# Lora_Artemis_schematic.net
KiCad netlist of a schematic drawn in EAGLE
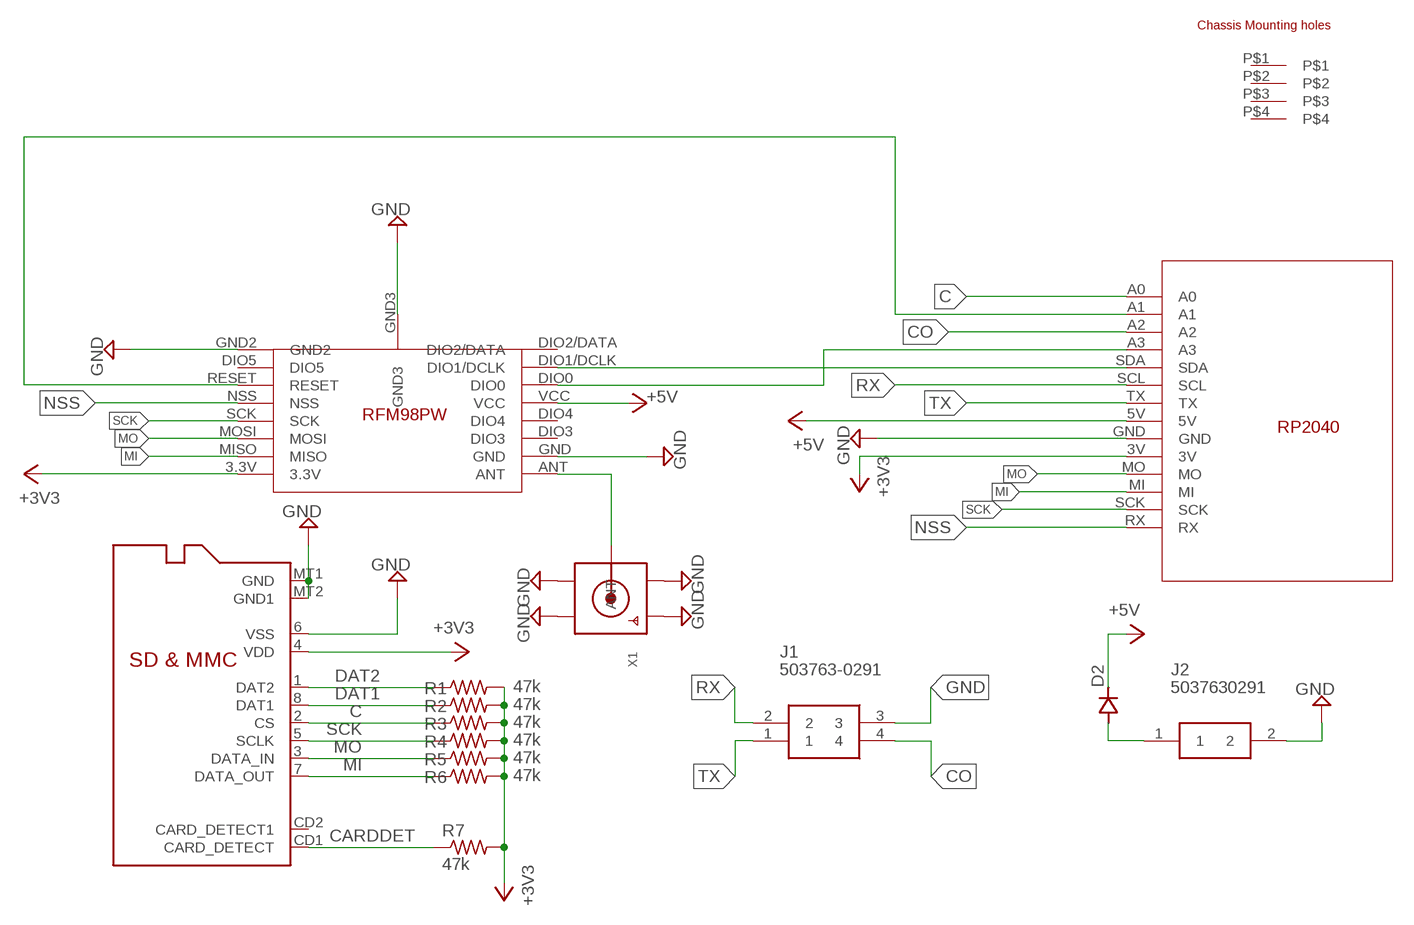
[diagram p0: schematic, sheet 1]

(export (version "E")
  (design (tool "Eeschema 10.0.6"))
  (components
    (comp (ref "D2")
      (value "DSOD323")
      (footprint "eagle-import:SOD323")
      (fields (field (name "MPN") "CDSOD323-T05C"))
      (libsource (lib "eagle-import") (part "DSOD323"))
    )
    (comp (ref "H1")
      (value "PC104_WCONN_2\"")
      (footprint "eagle-import:PC104_WCONN_2")
      (libsource (lib "eagle-import") (part "PC104_WCONN_2{dblquote}"))
    )
    (comp (ref "J1")
      (value "503763-0291")
      (footprint "eagle-import:5037630291")
      (fields (field (name "MOUSER_PART_NUMBER") "538-503763-0291"))
      (libsource (lib "eagle-import") (part "503763-0291"))
    )
    (comp (ref "J2")
      (value "5037630291")
      (footprint "eagle-import:5037630291")
      (libsource (lib "eagle-import") (part "5037630291"))
    )
    (comp (ref "R1")
      (value "47k")
      (footprint "eagle-import:M0805")
      (libsource (lib "eagle-import") (part "R-US_M0805"))
    )
    (comp (ref "R2")
      (value "47k")
      (footprint "eagle-import:M0805")
      (libsource (lib "eagle-import") (part "R-US_M0805"))
    )
    (comp (ref "R3")
      (value "47k")
      (footprint "eagle-import:M0805")
      (libsource (lib "eagle-import") (part "R-US_M0805"))
    )
    (comp (ref "R4")
      (value "47k")
      (footprint "eagle-import:M0805")
      (libsource (lib "eagle-import") (part "R-US_M0805"))
    )
    (comp (ref "R5")
      (value "47k")
      (footprint "eagle-import:M0805")
      (libsource (lib "eagle-import") (part "R-US_M0805"))
    )
    (comp (ref "R6")
      (value "47k")
      (footprint "eagle-import:M0805")
      (libsource (lib "eagle-import") (part "R-US_M0805"))
    )
    (comp (ref "R7")
      (value "47k")
      (footprint "eagle-import:M0805")
      (libsource (lib "eagle-import") (part "R-US_M0805"))
    )
    (comp (ref "U$1")
      (value "QTPY2040")
      (footprint "eagle-import:QTPY2040")
      (libsource (lib "eagle-import") (part "QTPY2040"))
    )
    (comp (ref "U$2")
      (value "RFM98PW")
      (footprint "eagle-import:RFM98PW")
      (libsource (lib "eagle-import") (part "RFM98PW"))
    )
    (comp (ref "U$3")
      (value "MICROSD")
      (footprint "eagle-import:MICROSD")
      (libsource (lib "eagle-import") (part "MICROSD"))
    )
    (comp (ref "X1")
      (value "SMACONNECTOR")
      (footprint "eagle-import:SMA90_DIP")
      (libsource (lib "eagle-import") (part "SMACONNECTOR"))
    )
  )
  (nets
    (net (code "1") (name "+3V3") (class "Default")
      (node (ref "R1") (pin "2") (pinfunction "2_2") (pintype "passive"))
      (node (ref "R2") (pin "2") (pinfunction "2_2") (pintype "passive"))
      (node (ref "R3") (pin "2") (pinfunction "2_2") (pintype "passive"))
      (node (ref "R4") (pin "2") (pinfunction "2_2") (pintype "passive"))
      (node (ref "R5") (pin "2") (pinfunction "2_2") (pintype "passive"))
      (node (ref "R6") (pin "2") (pinfunction "2_2") (pintype "passive"))
      (node (ref "R7") (pin "2") (pinfunction "2_2") (pintype "passive"))
      (node (ref "U$1") (pin "3V") (pinfunction "3V_3V") (pintype "bidirectional"))
      (node (ref "U$2") (pin "3.3V") (pinfunction "3.3V_3.3V") (pintype "bidirectional"))
      (node (ref "U$3") (pin "4") (pinfunction "VDD_4") (pintype "power_in"))
    )
    (net (code "2") (name "+5V") (class "Default")
      (node (ref "D2") (pin "1") (pinfunction "C_1") (pintype "passive"))
      (node (ref "U$1") (pin "5V") (pinfunction "5V_5V") (pintype "bidirectional"))
      (node (ref "U$2") (pin "VCC") (pinfunction "VCC_VCC") (pintype "bidirectional"))
    )
    (net (code "3") (name "/CARDDET") (class "Default")
      (node (ref "R7") (pin "1") (pinfunction "1_1") (pintype "passive"))
      (node (ref "U$3") (pin "CD1") (pinfunction "CARD_DETECT_CD1") (pintype "passive"))
    )
    (net (code "4") (name "/DAT1") (class "Default")
      (node (ref "R2") (pin "1") (pinfunction "1_1") (pintype "passive"))
      (node (ref "U$3") (pin "8") (pinfunction "DAT1_8") (pintype "bidirectional"))
    )
    (net (code "5") (name "/DAT2") (class "Default")
      (node (ref "R1") (pin "1") (pinfunction "1_1") (pintype "passive"))
      (node (ref "U$3") (pin "1") (pinfunction "DAT2_1") (pintype "bidirectional"))
    )
    (net (code "6") (name "C") (class "Default")
      (node (ref "R3") (pin "1") (pinfunction "1_1") (pintype "passive"))
      (node (ref "U$1") (pin "A0") (pinfunction "A0_A0") (pintype "bidirectional"))
      (node (ref "U$3") (pin "2") (pinfunction "CS_2") (pintype "input"))
    )
    (net (code "7") (name "CO") (class "Default")
      (node (ref "J1") (pin "4") (pinfunction "4_4") (pintype "bidirectional"))
      (node (ref "U$1") (pin "A2") (pinfunction "A2_A2") (pintype "bidirectional"))
    )
    (net (code "8") (name "GND") (class "Default")
      (node (ref "J1") (pin "3") (pinfunction "3_3") (pintype "bidirectional"))
      (node (ref "J2") (pin "2") (pinfunction "2_2") (pintype "bidirectional"))
      (node (ref "U$1") (pin "GND") (pinfunction "GND_GND") (pintype "bidirectional"))
      (node (ref "U$2") (pin "GND") (pinfunction "GND_GND") (pintype "bidirectional"))
      (node (ref "U$2") (pin "GND2") (pinfunction "GND2_GND2") (pintype "bidirectional"))
      (node (ref "U$2") (pin "GND3") (pinfunction "GND3_GND3") (pintype "bidirectional"))
      (node (ref "U$3") (pin "6") (pinfunction "VSS_6") (pintype "power_in"))
      (node (ref "U$3") (pin "MT1") (pinfunction "GND_MT1") (pintype "power_in"))
      (node (ref "U$3") (pin "MT2") (pinfunction "GND1_MT2") (pintype "power_in"))
      (node (ref "X1") (pin "GND1") (pinfunction "GND1_GND1") (pintype "power_in"))
      (node (ref "X1") (pin "GND2") (pinfunction "GND2_GND2") (pintype "power_in"))
      (node (ref "X1") (pin "GND3") (pinfunction "GND3_GND3") (pintype "power_in"))
      (node (ref "X1") (pin "GND4") (pinfunction "GND4_GND4") (pintype "power_in"))
    )
    (net (code "9") (name "MI") (class "Default")
      (node (ref "R6") (pin "1") (pinfunction "1_1") (pintype "passive"))
      (node (ref "U$1") (pin "MI") (pinfunction "MI_MI") (pintype "bidirectional"))
      (node (ref "U$2") (pin "MISO") (pinfunction "MISO_MISO") (pintype "bidirectional"))
      (node (ref "U$3") (pin "7") (pinfunction "DATA_OUT_7") (pintype "output"))
    )
    (net (code "10") (name "MO") (class "Default")
      (node (ref "R5") (pin "1") (pinfunction "1_1") (pintype "passive"))
      (node (ref "U$1") (pin "MO") (pinfunction "MO_MO") (pintype "bidirectional"))
      (node (ref "U$2") (pin "MOSI") (pinfunction "MOSI_MOSI") (pintype "bidirectional"))
      (node (ref "U$3") (pin "3") (pinfunction "DATA_IN_3") (pintype "input"))
    )
    (net (code "11") (name "NSS") (class "Default")
      (node (ref "U$1") (pin "RX") (pinfunction "RX_RX") (pintype "bidirectional"))
      (node (ref "U$2") (pin "NSS") (pinfunction "NSS_NSS") (pintype "bidirectional"))
    )
    (net (code "12") (name "Net-(D2-A)") (class "Default")
      (node (ref "D2") (pin "2") (pinfunction "A_2") (pintype "passive"))
      (node (ref "J2") (pin "1") (pinfunction "1_1") (pintype "bidirectional"))
    )
    (net (code "13") (name "Net-(U$1-PadA1)") (class "Default")
      (node (ref "U$1") (pin "A1") (pinfunction "A1_A1") (pintype "bidirectional"))
      (node (ref "U$2") (pin "RESET") (pinfunction "RESET_RESET") (pintype "bidirectional"))
    )
    (net (code "14") (name "Net-(U$1-PadA3)") (class "Default")
      (node (ref "U$1") (pin "A3") (pinfunction "A3_A3") (pintype "bidirectional"))
      (node (ref "U$2") (pin "DIO0") (pinfunction "DIO0_DIO0") (pintype "bidirectional"))
    )
    (net (code "15") (name "Net-(U$1-PadSDA)") (class "Default")
      (node (ref "U$1") (pin "SDA") (pinfunction "SDA_SDA") (pintype "bidirectional"))
      (node (ref "U$2") (pin "DIO1/DCLK") (pinfunction "DIO1/DCLK_DIO1/DCLK") (pintype "bidirectional"))
    )
    (net (code "16") (name "Net-(X1-ANT)") (class "Default")
      (node (ref "U$2") (pin "ANT") (pinfunction "ANT_ANT") (pintype "bidirectional"))
      (node (ref "X1") (pin "ANTENNA") (pinfunction "ANT_ANTENNA") (pintype "bidirectional"))
    )
    (net (code "17") (name "RX") (class "Default")
      (node (ref "J1") (pin "2") (pinfunction "2_2") (pintype "bidirectional"))
      (node (ref "U$1") (pin "SCL") (pinfunction "SCL_SCL") (pintype "bidirectional"))
    )
    (net (code "18") (name "SCK") (class "Default")
      (node (ref "R4") (pin "1") (pinfunction "1_1") (pintype "passive"))
      (node (ref "U$1") (pin "SCK") (pinfunction "SCK_SCK") (pintype "bidirectional"))
      (node (ref "U$2") (pin "SCK") (pinfunction "SCK_SCK") (pintype "bidirectional"))
      (node (ref "U$3") (pin "5") (pinfunction "SCLK_5") (pintype "input"))
    )
    (net (code "19") (name "TX") (class "Default")
      (node (ref "J1") (pin "1") (pinfunction "1_1") (pintype "bidirectional"))
      (node (ref "U$1") (pin "TX") (pinfunction "TX_TX") (pintype "bidirectional"))
    )
    (net (code "20") (name "unconnected-(H1-PadP$1)") (class "Default")
      (node (ref "H1") (pin "P$1") (pinfunction "P$1_P$1") (pintype "bidirectional"))
    )
    (net (code "21") (name "unconnected-(H1-PadP$2)") (class "Default")
      (node (ref "H1") (pin "P$2") (pinfunction "P$2_P$2") (pintype "bidirectional"))
    )
    (net (code "22") (name "unconnected-(H1-PadP$3)") (class "Default")
      (node (ref "H1") (pin "P$3") (pinfunction "P$3_P$3") (pintype "bidirectional"))
    )
    (net (code "23") (name "unconnected-(H1-PadP$4)") (class "Default")
      (node (ref "H1") (pin "P$4") (pinfunction "P$4_P$4") (pintype "bidirectional"))
    )
    (net (code "24") (name "unconnected-(U$2-PadDIO2{slash}DATA)") (class "Default")
      (node (ref "U$2") (pin "DIO2/DATA") (pinfunction "DIO2/DATA_DIO2/DATA") (pintype "bidirectional"))
    )
    (net (code "25") (name "unconnected-(U$2-PadDIO3)") (class "Default")
      (node (ref "U$2") (pin "DIO3") (pinfunction "DIO3_DIO3") (pintype "bidirectional"))
    )
    (net (code "26") (name "unconnected-(U$2-PadDIO4)") (class "Default")
      (node (ref "U$2") (pin "DIO4") (pinfunction "DIO4_DIO4") (pintype "bidirectional"))
    )
    (net (code "27") (name "unconnected-(U$2-PadDIO5)") (class "Default")
      (node (ref "U$2") (pin "DIO5") (pinfunction "DIO5_DIO5") (pintype "bidirectional"))
    )
    (net (code "28") (name "unconnected-(U$3-CARD_DETECT1-PadCD2)") (class "Default")
      (node (ref "U$3") (pin "CD2") (pinfunction "CARD_DETECT1_CD2") (pintype "passive"))
    )
  )
)
